# CCD.net
KiCad netlist of a schematic drawn in EAGLE
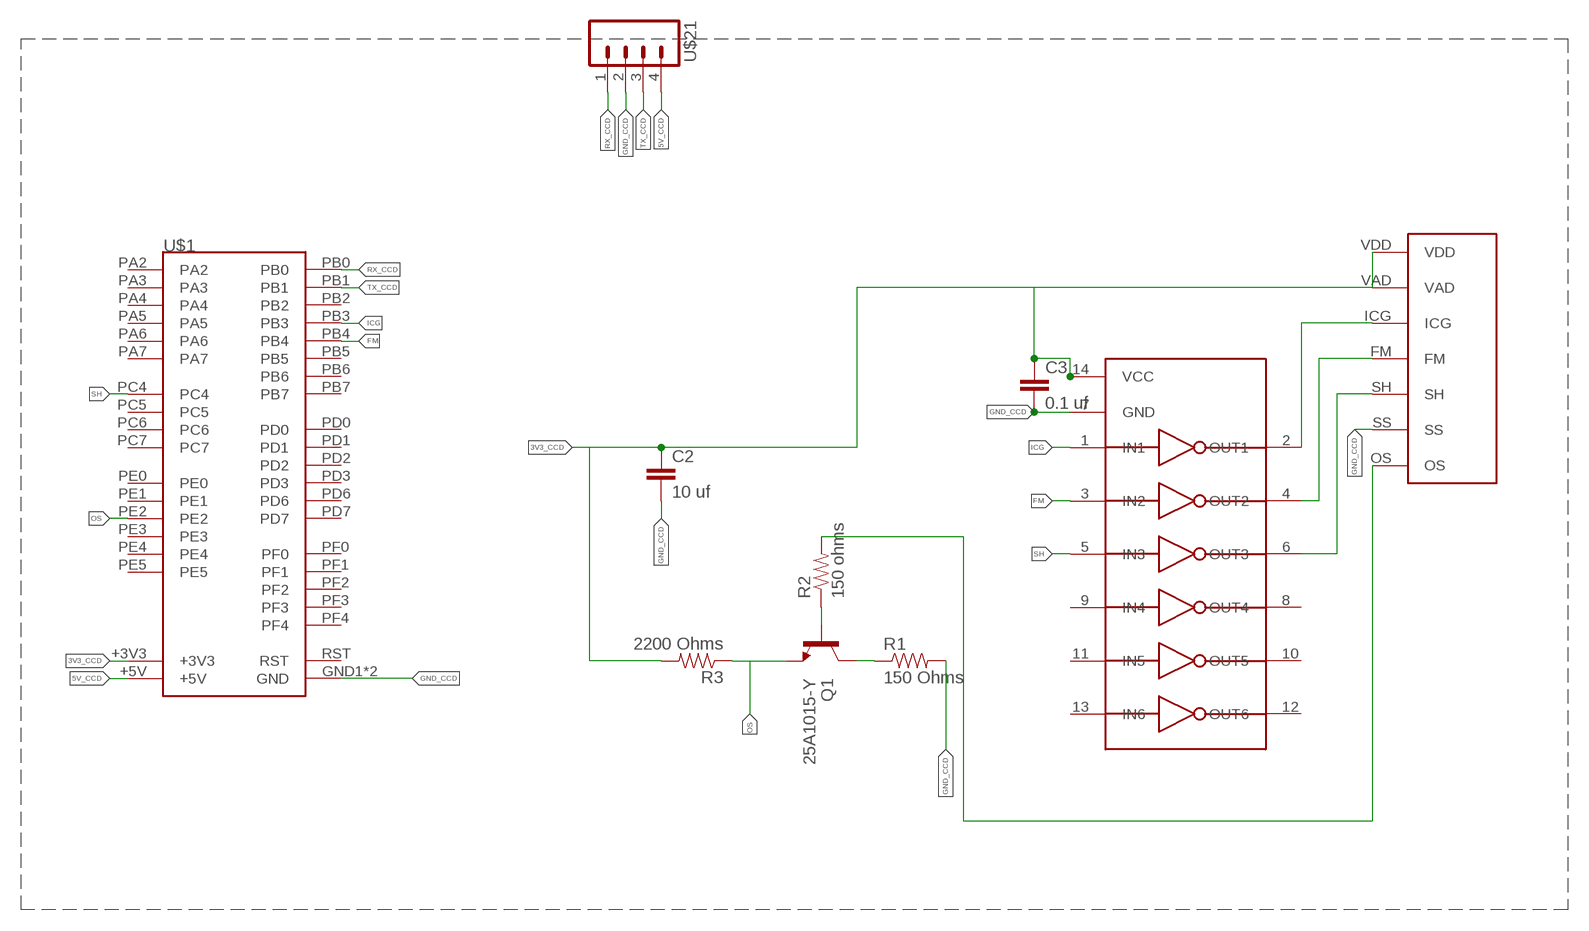
[diagram p0: schematic, sheet 1]

(export (version "E")
  (design (tool "Eeschema 10.0.6"))
  (components
    (comp (ref "C2")
      (value "10 uf")
      (footprint "eagle-import:0603-CAP")
      (libsource (lib "eagle-import") (part "CAP0603-CAP"))
    )
    (comp (ref "C3")
      (value "0.1 uf")
      (footprint "eagle-import:0603-CAP")
      (libsource (lib "eagle-import") (part "CAP0603-CAP"))
    )
    (comp (ref "Q1")
      (value "25A1015-Y")
      (footprint "eagle-import:TO-92-AMMO")
      (libsource (lib "eagle-import") (part "TRANSISTOR_NPNBC547"))
    )
    (comp (ref "R1")
      (value "150 Ohms")
      (footprint "eagle-import:0603-RES")
      (libsource (lib "eagle-import") (part "RESISTOR0603-RES"))
    )
    (comp (ref "R2")
      (value "150 ohms")
      (footprint "eagle-import:0603-RES")
      (libsource (lib "eagle-import") (part "RESISTOR0603-RES"))
    )
    (comp (ref "R3")
      (value "2200 Ohms")
      (footprint "eagle-import:0603-RES")
      (libsource (lib "eagle-import") (part "RESISTOR0603-RES"))
    )
    (comp (ref "U$1")
      (value "TIVA-C")
      (footprint "eagle-import:TIVA-C")
      (libsource (lib "eagle-import") (part "TIVA-C"))
    )
    (comp (ref "U$11")
      (value "TC74HC04AP")
      (footprint "eagle-import:DIP14")
      (libsource (lib "eagle-import") (part "TC74HC04AP"))
    )
    (comp (ref "U$12")
      (value "TCD1304DG")
      (footprint "eagle-import:CCD_PACKAGE")
      (libsource (lib "eagle-import") (part "TCD1304DG"))
    )
    (comp (ref "U$21")
      (value "M04")
      (footprint "eagle-import:MOLEX_0436500400")
      (libsource (lib "eagle-import") (part "M04"))
    )
  )
  (nets
    (net (code "1") (name "/RST") (class "Default")
      (node (ref "U$1") (pin "RST") (pinfunction "RST_RST") (pintype "power_in"))
    )
    (net (code "2") (name "3V3_CCD") (class "Default")
      (node (ref "C2") (pin "1") (pinfunction "1_1") (pintype "passive"))
      (node (ref "C3") (pin "1") (pinfunction "1_1") (pintype "passive"))
      (node (ref "R3") (pin "2") (pinfunction "2_2") (pintype "passive"))
      (node (ref "U$1") (pin "+3V3") (pinfunction "+3V3_+3V3") (pintype "power_in"))
      (node (ref "U$11") (pin "14") (pinfunction "VCC_14") (pintype "bidirectional"))
      (node (ref "U$12") (pin "VAD") (pinfunction "VAD_VAD") (pintype "bidirectional"))
      (node (ref "U$12") (pin "VDD") (pinfunction "VDD_VDD") (pintype "bidirectional"))
    )
    (net (code "3") (name "5V_CCD") (class "Default")
      (node (ref "U$1") (pin "+5V") (pinfunction "+5V_+5V") (pintype "power_in"))
      (node (ref "U$21") (pin "4") (pinfunction "4_4") (pintype "passive"))
    )
    (net (code "4") (name "FM") (class "Default")
      (node (ref "U$1") (pin "PB4") (pinfunction "PB4_PB4") (pintype "bidirectional"))
      (node (ref "U$11") (pin "3") (pinfunction "IN2_3") (pintype "bidirectional"))
    )
    (net (code "5") (name "GND_CCD") (class "Default")
      (node (ref "C2") (pin "2") (pinfunction "2_2") (pintype "passive"))
      (node (ref "C3") (pin "2") (pinfunction "2_2") (pintype "passive"))
      (node (ref "R1") (pin "2") (pinfunction "2_2") (pintype "passive"))
      (node (ref "U$1") (pin "GND1") (pinfunction "GND_GND1") (pintype "power_in"))
      (node (ref "U$1") (pin "GND2") (pinfunction "GND_GND2") (pintype "power_in"))
      (node (ref "U$11") (pin "7") (pinfunction "GND_7") (pintype "bidirectional"))
      (node (ref "U$12") (pin "SS") (pinfunction "SS_SS") (pintype "bidirectional"))
      (node (ref "U$21") (pin "2") (pinfunction "2_2") (pintype "passive"))
    )
    (net (code "6") (name "ICG") (class "Default")
      (node (ref "U$1") (pin "PB3") (pinfunction "PB3_PB3") (pintype "bidirectional"))
      (node (ref "U$11") (pin "1") (pinfunction "IN1_1") (pintype "bidirectional"))
    )
    (net (code "7") (name "Net-(Q1-B)") (class "Default")
      (node (ref "Q1") (pin "2") (pinfunction "B_2") (pintype "passive"))
      (node (ref "R2") (pin "1") (pinfunction "1_1") (pintype "passive"))
    )
    (net (code "8") (name "Net-(Q1-C)") (class "Default")
      (node (ref "Q1") (pin "1") (pinfunction "C_1") (pintype "passive"))
      (node (ref "R1") (pin "1") (pinfunction "1_1") (pintype "passive"))
    )
    (net (code "9") (name "Net-(R2-Pad2)") (class "Default")
      (node (ref "R2") (pin "2") (pinfunction "2_2") (pintype "passive"))
      (node (ref "U$12") (pin "OS") (pinfunction "OS_OS") (pintype "bidirectional"))
    )
    (net (code "10") (name "Net-(U$11-OUT1)") (class "Default")
      (node (ref "U$11") (pin "2") (pinfunction "OUT1_2") (pintype "bidirectional"))
      (node (ref "U$12") (pin "ICG") (pinfunction "ICG_ICG") (pintype "bidirectional"))
    )
    (net (code "11") (name "Net-(U$11-OUT2)") (class "Default")
      (node (ref "U$11") (pin "4") (pinfunction "OUT2_4") (pintype "bidirectional"))
      (node (ref "U$12") (pin "FM") (pinfunction "FM_FM") (pintype "bidirectional"))
    )
    (net (code "12") (name "Net-(U$11-OUT3)") (class "Default")
      (node (ref "U$11") (pin "6") (pinfunction "OUT3_6") (pintype "bidirectional"))
      (node (ref "U$12") (pin "SH") (pinfunction "SH_SH") (pintype "bidirectional"))
    )
    (net (code "13") (name "OS") (class "Default")
      (node (ref "Q1") (pin "3") (pinfunction "E_3") (pintype "passive"))
      (node (ref "R3") (pin "1") (pinfunction "1_1") (pintype "passive"))
      (node (ref "U$1") (pin "PE2") (pinfunction "PE2_PE2") (pintype "bidirectional"))
    )
    (net (code "14") (name "RX_CCD") (class "Default")
      (node (ref "U$1") (pin "PB0") (pinfunction "PB0_PB0") (pintype "bidirectional"))
      (node (ref "U$21") (pin "1") (pinfunction "1_1") (pintype "passive"))
    )
    (net (code "15") (name "SH") (class "Default")
      (node (ref "U$1") (pin "PC4") (pinfunction "PC4_PC4") (pintype "bidirectional"))
      (node (ref "U$11") (pin "5") (pinfunction "IN3_5") (pintype "bidirectional"))
    )
    (net (code "16") (name "TX_CCD") (class "Default")
      (node (ref "U$1") (pin "PB1") (pinfunction "PB1_PB1") (pintype "bidirectional"))
      (node (ref "U$21") (pin "3") (pinfunction "3_3") (pintype "passive"))
    )
    (net (code "17") (name "unconnected-(U$1-PadPA2)") (class "Default")
      (node (ref "U$1") (pin "PA2") (pinfunction "PA2_PA2") (pintype "bidirectional"))
    )
    (net (code "18") (name "unconnected-(U$1-PadPA3)") (class "Default")
      (node (ref "U$1") (pin "PA3") (pinfunction "PA3_PA3") (pintype "bidirectional"))
    )
    (net (code "19") (name "unconnected-(U$1-PadPA4)") (class "Default")
      (node (ref "U$1") (pin "PA4") (pinfunction "PA4_PA4") (pintype "bidirectional"))
    )
    (net (code "20") (name "unconnected-(U$1-PadPA5)") (class "Default")
      (node (ref "U$1") (pin "PA5") (pinfunction "PA5_PA5") (pintype "bidirectional"))
    )
    (net (code "21") (name "unconnected-(U$1-PadPA6)") (class "Default")
      (node (ref "U$1") (pin "PA6") (pinfunction "PA6_PA6") (pintype "bidirectional"))
    )
    (net (code "22") (name "unconnected-(U$1-PadPA7)") (class "Default")
      (node (ref "U$1") (pin "PA7") (pinfunction "PA7_PA7") (pintype "bidirectional"))
    )
    (net (code "23") (name "unconnected-(U$1-PadPB2)") (class "Default")
      (node (ref "U$1") (pin "PB2") (pinfunction "PB2_PB2") (pintype "bidirectional"))
    )
    (net (code "24") (name "unconnected-(U$1-PadPB5)") (class "Default")
      (node (ref "U$1") (pin "PB5") (pinfunction "PB5_PB5") (pintype "bidirectional"))
    )
    (net (code "25") (name "unconnected-(U$1-PadPB6)") (class "Default")
      (node (ref "U$1") (pin "PB6") (pinfunction "PB6_PB6") (pintype "bidirectional"))
    )
    (net (code "26") (name "unconnected-(U$1-PadPB7)") (class "Default")
      (node (ref "U$1") (pin "PB7") (pinfunction "PB7_PB7") (pintype "bidirectional"))
    )
    (net (code "27") (name "unconnected-(U$1-PadPC5)") (class "Default")
      (node (ref "U$1") (pin "PC5") (pinfunction "PC5_PC5") (pintype "bidirectional"))
    )
    (net (code "28") (name "unconnected-(U$1-PadPC6)") (class "Default")
      (node (ref "U$1") (pin "PC6") (pinfunction "PC6_PC6") (pintype "bidirectional"))
    )
    (net (code "29") (name "unconnected-(U$1-PadPC7)") (class "Default")
      (node (ref "U$1") (pin "PC7") (pinfunction "PC7_PC7") (pintype "bidirectional"))
    )
    (net (code "30") (name "unconnected-(U$1-PadPD0)") (class "Default")
      (node (ref "U$1") (pin "PD0") (pinfunction "PD0_PD0") (pintype "bidirectional"))
    )
    (net (code "31") (name "unconnected-(U$1-PadPD1)") (class "Default")
      (node (ref "U$1") (pin "PD1") (pinfunction "PD1_PD1") (pintype "bidirectional"))
    )
    (net (code "32") (name "unconnected-(U$1-PadPD2)") (class "Default")
      (node (ref "U$1") (pin "PD2") (pinfunction "PD2_PD2") (pintype "bidirectional"))
    )
    (net (code "33") (name "unconnected-(U$1-PadPD3)") (class "Default")
      (node (ref "U$1") (pin "PD3") (pinfunction "PD3_PD3") (pintype "bidirectional"))
    )
    (net (code "34") (name "unconnected-(U$1-PadPD6)") (class "Default")
      (node (ref "U$1") (pin "PD6") (pinfunction "PD6_PD6") (pintype "bidirectional"))
    )
    (net (code "35") (name "unconnected-(U$1-PadPD7)") (class "Default")
      (node (ref "U$1") (pin "PD7") (pinfunction "PD7_PD7") (pintype "bidirectional"))
    )
    (net (code "36") (name "unconnected-(U$1-PadPE0)") (class "Default")
      (node (ref "U$1") (pin "PE0") (pinfunction "PE0_PE0") (pintype "bidirectional"))
    )
    (net (code "37") (name "unconnected-(U$1-PadPE1)") (class "Default")
      (node (ref "U$1") (pin "PE1") (pinfunction "PE1_PE1") (pintype "bidirectional"))
    )
    (net (code "38") (name "unconnected-(U$1-PadPE3)") (class "Default")
      (node (ref "U$1") (pin "PE3") (pinfunction "PE3_PE3") (pintype "bidirectional"))
    )
    (net (code "39") (name "unconnected-(U$1-PadPE4)") (class "Default")
      (node (ref "U$1") (pin "PE4") (pinfunction "PE4_PE4") (pintype "bidirectional"))
    )
    (net (code "40") (name "unconnected-(U$1-PadPE5)") (class "Default")
      (node (ref "U$1") (pin "PE5") (pinfunction "PE5_PE5") (pintype "bidirectional"))
    )
    (net (code "41") (name "unconnected-(U$1-PadPF0)") (class "Default")
      (node (ref "U$1") (pin "PF0") (pinfunction "PF0_PF0") (pintype "bidirectional"))
    )
    (net (code "42") (name "unconnected-(U$1-PadPF1)") (class "Default")
      (node (ref "U$1") (pin "PF1") (pinfunction "PF1_PF1") (pintype "bidirectional"))
    )
    (net (code "43") (name "unconnected-(U$1-PadPF2)") (class "Default")
      (node (ref "U$1") (pin "PF2") (pinfunction "PF2_PF2") (pintype "bidirectional"))
    )
    (net (code "44") (name "unconnected-(U$1-PadPF3)") (class "Default")
      (node (ref "U$1") (pin "PF3") (pinfunction "PF3_PF3") (pintype "bidirectional"))
    )
    (net (code "45") (name "unconnected-(U$1-PadPF4)") (class "Default")
      (node (ref "U$1") (pin "PF4") (pinfunction "PF4_PF4") (pintype "bidirectional"))
    )
    (net (code "46") (name "unconnected-(U$11-IN4-Pad9)") (class "Default")
      (node (ref "U$11") (pin "9") (pinfunction "IN4_9") (pintype "bidirectional"))
    )
    (net (code "47") (name "unconnected-(U$11-IN5-Pad11)") (class "Default")
      (node (ref "U$11") (pin "11") (pinfunction "IN5_11") (pintype "bidirectional"))
    )
    (net (code "48") (name "unconnected-(U$11-IN6-Pad13)") (class "Default")
      (node (ref "U$11") (pin "13") (pinfunction "IN6_13") (pintype "bidirectional"))
    )
    (net (code "49") (name "unconnected-(U$11-OUT4-Pad8)") (class "Default")
      (node (ref "U$11") (pin "8") (pinfunction "OUT4_8") (pintype "bidirectional"))
    )
    (net (code "50") (name "unconnected-(U$11-OUT5-Pad10)") (class "Default")
      (node (ref "U$11") (pin "10") (pinfunction "OUT5_10") (pintype "bidirectional"))
    )
    (net (code "51") (name "unconnected-(U$11-OUT6-Pad12)") (class "Default")
      (node (ref "U$11") (pin "12") (pinfunction "OUT6_12") (pintype "bidirectional"))
    )
  )
)
